# eom_test_pcb_v2.net
KiCad netlist of a schematic drawn in EAGLE
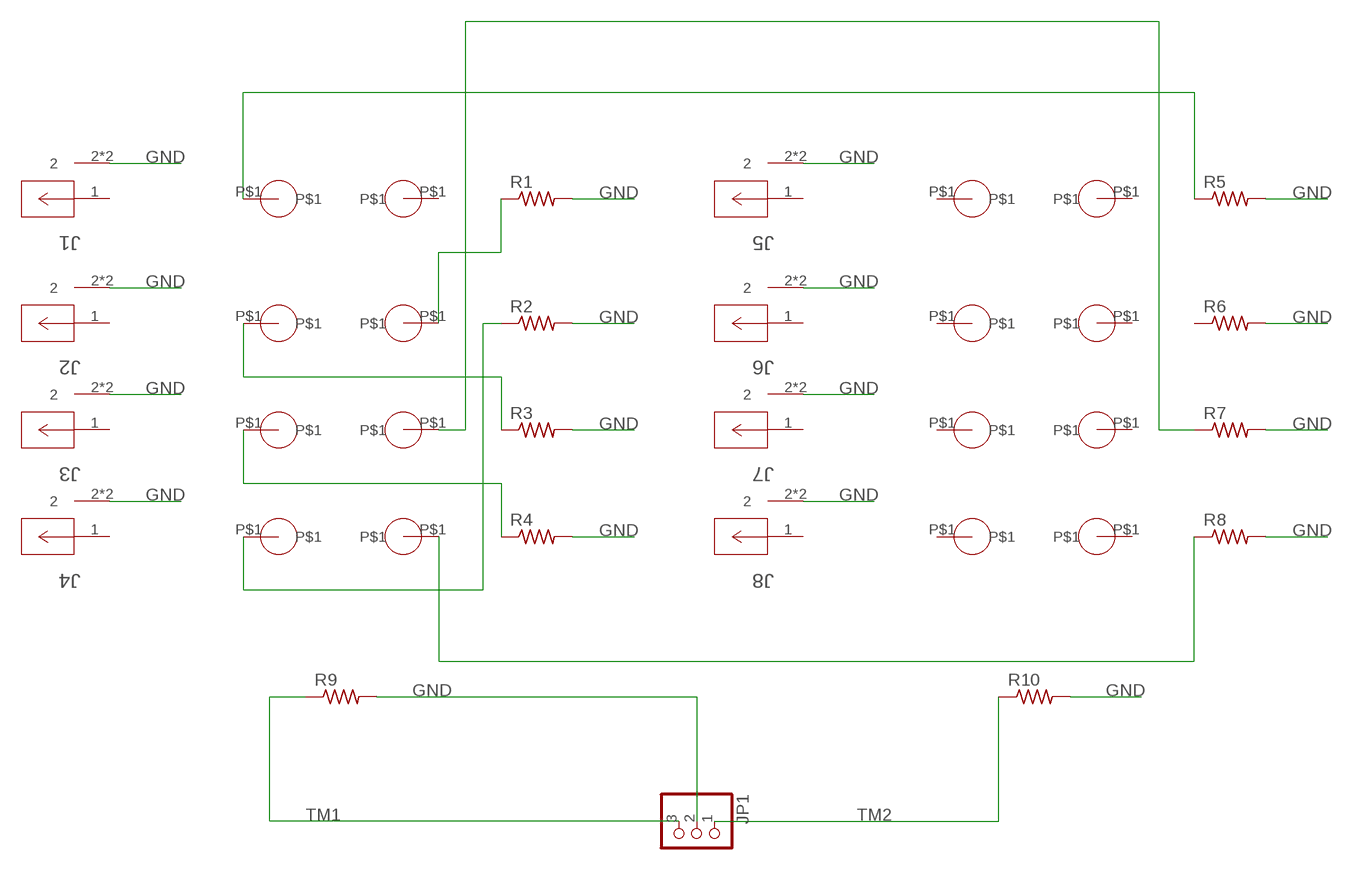
[diagram p0: schematic, sheet 1]

(export (version "E")
  (design (tool "Eeschema 10.0.6"))
  (components
    (comp (ref "J1")
      (value "142-0711-821")
      (footprint "eagle-import:CONN_142-0711-821_CIN")
      (fields (field (name "COPYRIGHT") "Copyright (C) 2021 Ultra Librarian. All rights reserved."))
      (libsource (lib "eagle-import") (part "142-0711-821"))
    )
    (comp (ref "J2")
      (value "142-0711-821")
      (footprint "eagle-import:CONN_142-0711-821_CIN")
      (fields (field (name "COPYRIGHT") "Copyright (C) 2021 Ultra Librarian. All rights reserved."))
      (libsource (lib "eagle-import") (part "142-0711-821"))
    )
    (comp (ref "J3")
      (value "142-0711-821")
      (footprint "eagle-import:CONN_142-0711-821_CIN")
      (fields (field (name "COPYRIGHT") "Copyright (C) 2021 Ultra Librarian. All rights reserved."))
      (libsource (lib "eagle-import") (part "142-0711-821"))
    )
    (comp (ref "J4")
      (value "142-0711-821")
      (footprint "eagle-import:CONN_142-0711-821_CIN")
      (fields (field (name "COPYRIGHT") "Copyright (C) 2021 Ultra Librarian. All rights reserved."))
      (libsource (lib "eagle-import") (part "142-0711-821"))
    )
    (comp (ref "J5")
      (value "142-0711-821")
      (footprint "eagle-import:CONN_142-0711-821_CIN")
      (fields (field (name "COPYRIGHT") "Copyright (C) 2021 Ultra Librarian. All rights reserved."))
      (libsource (lib "eagle-import") (part "142-0711-821"))
    )
    (comp (ref "J6")
      (value "142-0711-821")
      (footprint "eagle-import:CONN_142-0711-821_CIN")
      (fields (field (name "COPYRIGHT") "Copyright (C) 2021 Ultra Librarian. All rights reserved."))
      (libsource (lib "eagle-import") (part "142-0711-821"))
    )
    (comp (ref "J7")
      (value "142-0711-821")
      (footprint "eagle-import:CONN_142-0711-821_CIN")
      (fields (field (name "COPYRIGHT") "Copyright (C) 2021 Ultra Librarian. All rights reserved."))
      (libsource (lib "eagle-import") (part "142-0711-821"))
    )
    (comp (ref "J8")
      (value "142-0711-821")
      (footprint "eagle-import:CONN_142-0711-821_CIN")
      (fields (field (name "COPYRIGHT") "Copyright (C) 2021 Ultra Librarian. All rights reserved."))
      (libsource (lib "eagle-import") (part "142-0711-821"))
    )
    (comp (ref "JP1")
      (value "PINHD-1X3")
      (footprint "eagle-import:1X03")
      (libsource (lib "eagle-import") (part "PINHD-1X3"))
    )
    (comp (ref "R1")
      (value "R-US_M1206")
      (footprint "eagle-import:M1206")
      (libsource (lib "eagle-import") (part "R-US_M1206"))
    )
    (comp (ref "R2")
      (value "R-US_M1206")
      (footprint "eagle-import:M1206")
      (libsource (lib "eagle-import") (part "R-US_M1206"))
    )
    (comp (ref "R3")
      (value "R-US_M1206")
      (footprint "eagle-import:M1206")
      (libsource (lib "eagle-import") (part "R-US_M1206"))
    )
    (comp (ref "R4")
      (value "R-US_M1206")
      (footprint "eagle-import:M1206")
      (libsource (lib "eagle-import") (part "R-US_M1206"))
    )
    (comp (ref "R5")
      (value "R-US_M1206")
      (footprint "eagle-import:M1206")
      (libsource (lib "eagle-import") (part "R-US_M1206"))
    )
    (comp (ref "R6")
      (value "R-US_M1206")
      (footprint "eagle-import:M1206")
      (libsource (lib "eagle-import") (part "R-US_M1206"))
    )
    (comp (ref "R7")
      (value "R-US_M1206")
      (footprint "eagle-import:M1206")
      (libsource (lib "eagle-import") (part "R-US_M1206"))
    )
    (comp (ref "R8")
      (value "R-US_M1206")
      (footprint "eagle-import:M1206")
      (libsource (lib "eagle-import") (part "R-US_M1206"))
    )
    (comp (ref "R9")
      (value "R-US_R0402")
      (footprint "eagle-import:R0402")
      (libsource (lib "eagle-import") (part "adafruit_420_R-US_R0402"))
    )
    (comp (ref "R10")
      (value "R-US_R0402")
      (footprint "eagle-import:R0402")
      (libsource (lib "eagle-import") (part "adafruit_420_R-US_R0402"))
    )
    (comp (ref "U$1")
      (value "SIGNAL_BONDING_DEVICE")
      (footprint "eagle-import:SIGNAL_BONDING_PAD")
      (libsource (lib "eagle-import") (part "SIGNAL_BONDING_DEVICE"))
    )
    (comp (ref "U$2")
      (value "SIGNAL_BONDING_DEVICE")
      (footprint "eagle-import:SIGNAL_BONDING_PAD")
      (libsource (lib "eagle-import") (part "SIGNAL_BONDING_DEVICE"))
    )
    (comp (ref "U$3")
      (value "SIGNAL_BONDING_DEVICE")
      (footprint "eagle-import:SIGNAL_BONDING_PAD")
      (libsource (lib "eagle-import") (part "SIGNAL_BONDING_DEVICE"))
    )
    (comp (ref "U$4")
      (value "SIGNAL_BONDING_DEVICE")
      (footprint "eagle-import:SIGNAL_BONDING_PAD")
      (libsource (lib "eagle-import") (part "SIGNAL_BONDING_DEVICE"))
    )
    (comp (ref "U$5")
      (value "SIGNAL_BONDING_DEVICE")
      (footprint "eagle-import:SIGNAL_BONDING_PAD")
      (libsource (lib "eagle-import") (part "SIGNAL_BONDING_DEVICE"))
    )
    (comp (ref "U$6")
      (value "SIGNAL_BONDING_DEVICE")
      (footprint "eagle-import:SIGNAL_BONDING_PAD")
      (libsource (lib "eagle-import") (part "SIGNAL_BONDING_DEVICE"))
    )
    (comp (ref "U$7")
      (value "SIGNAL_BONDING_DEVICE")
      (footprint "eagle-import:SIGNAL_BONDING_PAD")
      (libsource (lib "eagle-import") (part "SIGNAL_BONDING_DEVICE"))
    )
    (comp (ref "U$8")
      (value "SIGNAL_BONDING_DEVICE")
      (footprint "eagle-import:SIGNAL_BONDING_PAD")
      (libsource (lib "eagle-import") (part "SIGNAL_BONDING_DEVICE"))
    )
    (comp (ref "U$9")
      (value "SIGNAL_BONDING_DEVICE")
      (footprint "eagle-import:SIGNAL_BONDING_PAD")
      (libsource (lib "eagle-import") (part "SIGNAL_BONDING_DEVICE"))
    )
    (comp (ref "U$10")
      (value "SIGNAL_BONDING_DEVICE")
      (footprint "eagle-import:SIGNAL_BONDING_PAD")
      (libsource (lib "eagle-import") (part "SIGNAL_BONDING_DEVICE"))
    )
    (comp (ref "U$11")
      (value "SIGNAL_BONDING_DEVICE")
      (footprint "eagle-import:SIGNAL_BONDING_PAD")
      (libsource (lib "eagle-import") (part "SIGNAL_BONDING_DEVICE"))
    )
    (comp (ref "U$12")
      (value "SIGNAL_BONDING_DEVICE")
      (footprint "eagle-import:SIGNAL_BONDING_PAD")
      (libsource (lib "eagle-import") (part "SIGNAL_BONDING_DEVICE"))
    )
    (comp (ref "U$13")
      (value "SIGNAL_BONDING_DEVICE")
      (footprint "eagle-import:SIGNAL_BONDING_PAD")
      (libsource (lib "eagle-import") (part "SIGNAL_BONDING_DEVICE"))
    )
    (comp (ref "U$14")
      (value "SIGNAL_BONDING_DEVICE")
      (footprint "eagle-import:SIGNAL_BONDING_PAD")
      (libsource (lib "eagle-import") (part "SIGNAL_BONDING_DEVICE"))
    )
    (comp (ref "U$15")
      (value "SIGNAL_BONDING_DEVICE")
      (footprint "eagle-import:SIGNAL_BONDING_PAD")
      (libsource (lib "eagle-import") (part "SIGNAL_BONDING_DEVICE"))
    )
    (comp (ref "U$16")
      (value "SIGNAL_BONDING_DEVICE")
      (footprint "eagle-import:SIGNAL_BONDING_PAD")
      (libsource (lib "eagle-import") (part "SIGNAL_BONDING_DEVICE"))
    )
  )
  (nets
    (net (code "1") (name "/GND") (class "Default")
      (node (ref "J1") (pin "2") (pinfunction "2_2") (pintype "bidirectional"))
      (node (ref "J1") (pin "3") (pinfunction "2_3") (pintype "bidirectional"))
      (node (ref "J2") (pin "2") (pinfunction "2_2") (pintype "bidirectional"))
      (node (ref "J2") (pin "3") (pinfunction "2_3") (pintype "bidirectional"))
      (node (ref "J3") (pin "2") (pinfunction "2_2") (pintype "bidirectional"))
      (node (ref "J3") (pin "3") (pinfunction "2_3") (pintype "bidirectional"))
      (node (ref "J4") (pin "2") (pinfunction "2_2") (pintype "bidirectional"))
      (node (ref "J4") (pin "3") (pinfunction "2_3") (pintype "bidirectional"))
      (node (ref "J5") (pin "2") (pinfunction "2_2") (pintype "bidirectional"))
      (node (ref "J5") (pin "3") (pinfunction "2_3") (pintype "bidirectional"))
      (node (ref "J6") (pin "2") (pinfunction "2_2") (pintype "bidirectional"))
      (node (ref "J6") (pin "3") (pinfunction "2_3") (pintype "bidirectional"))
      (node (ref "J7") (pin "2") (pinfunction "2_2") (pintype "bidirectional"))
      (node (ref "J7") (pin "3") (pinfunction "2_3") (pintype "bidirectional"))
      (node (ref "J8") (pin "2") (pinfunction "2_2") (pintype "bidirectional"))
      (node (ref "J8") (pin "3") (pinfunction "2_3") (pintype "bidirectional"))
      (node (ref "JP1") (pin "2") (pinfunction "2_2") (pintype "passive"))
      (node (ref "R1") (pin "2") (pinfunction "2_2") (pintype "passive"))
      (node (ref "R10") (pin "2") (pinfunction "2_2") (pintype "passive"))
      (node (ref "R2") (pin "2") (pinfunction "2_2") (pintype "passive"))
      (node (ref "R3") (pin "2") (pinfunction "2_2") (pintype "passive"))
      (node (ref "R4") (pin "2") (pinfunction "2_2") (pintype "passive"))
      (node (ref "R5") (pin "2") (pinfunction "2_2") (pintype "passive"))
      (node (ref "R6") (pin "2") (pinfunction "2_2") (pintype "passive"))
      (node (ref "R7") (pin "2") (pinfunction "2_2") (pintype "passive"))
      (node (ref "R8") (pin "2") (pinfunction "2_2") (pintype "passive"))
      (node (ref "R9") (pin "2") (pinfunction "2_2") (pintype "passive"))
    )
    (net (code "2") (name "/TM1") (class "Default")
      (node (ref "JP1") (pin "3") (pinfunction "3_3") (pintype "passive"))
      (node (ref "R9") (pin "1") (pinfunction "1_1") (pintype "passive"))
    )
    (net (code "3") (name "/TM2") (class "Default")
      (node (ref "JP1") (pin "1") (pinfunction "1_1") (pintype "passive"))
      (node (ref "R10") (pin "1") (pinfunction "1_1") (pintype "passive"))
    )
    (net (code "4") (name "Net-(R1-Pad1)") (class "Default")
      (node (ref "R1") (pin "1") (pinfunction "1_1") (pintype "passive"))
      (node (ref "U$4") (pin "P$1") (pinfunction "P$1_P$1") (pintype "bidirectional"))
    )
    (net (code "5") (name "Net-(R2-Pad1)") (class "Default")
      (node (ref "R2") (pin "1") (pinfunction "1_1") (pintype "passive"))
      (node (ref "U$7") (pin "P$1") (pinfunction "P$1_P$1") (pintype "bidirectional"))
    )
    (net (code "6") (name "Net-(R3-Pad1)") (class "Default")
      (node (ref "R3") (pin "1") (pinfunction "1_1") (pintype "passive"))
      (node (ref "U$3") (pin "P$1") (pinfunction "P$1_P$1") (pintype "bidirectional"))
    )
    (net (code "7") (name "Net-(R4-Pad1)") (class "Default")
      (node (ref "R4") (pin "1") (pinfunction "1_1") (pintype "passive"))
      (node (ref "U$5") (pin "P$1") (pinfunction "P$1_P$1") (pintype "bidirectional"))
    )
    (net (code "8") (name "Net-(R5-Pad1)") (class "Default")
      (node (ref "R5") (pin "1") (pinfunction "1_1") (pintype "passive"))
      (node (ref "U$1") (pin "P$1") (pinfunction "P$1_P$1") (pintype "bidirectional"))
    )
    (net (code "9") (name "Net-(R7-Pad1)") (class "Default")
      (node (ref "R7") (pin "1") (pinfunction "1_1") (pintype "passive"))
      (node (ref "U$6") (pin "P$1") (pinfunction "P$1_P$1") (pintype "bidirectional"))
    )
    (net (code "10") (name "Net-(R8-Pad1)") (class "Default")
      (node (ref "R8") (pin "1") (pinfunction "1_1") (pintype "passive"))
      (node (ref "U$8") (pin "P$1") (pinfunction "P$1_P$1") (pintype "bidirectional"))
    )
    (net (code "11") (name "unconnected-(J1-Pad1)") (class "Default")
      (node (ref "J1") (pin "1") (pinfunction "1_1") (pintype "passive"))
    )
    (net (code "12") (name "unconnected-(J2-Pad1)") (class "Default")
      (node (ref "J2") (pin "1") (pinfunction "1_1") (pintype "passive"))
    )
    (net (code "13") (name "unconnected-(J3-Pad1)") (class "Default")
      (node (ref "J3") (pin "1") (pinfunction "1_1") (pintype "passive"))
    )
    (net (code "14") (name "unconnected-(J4-Pad1)") (class "Default")
      (node (ref "J4") (pin "1") (pinfunction "1_1") (pintype "passive"))
    )
    (net (code "15") (name "unconnected-(J5-Pad1)") (class "Default")
      (node (ref "J5") (pin "1") (pinfunction "1_1") (pintype "passive"))
    )
    (net (code "16") (name "unconnected-(J6-Pad1)") (class "Default")
      (node (ref "J6") (pin "1") (pinfunction "1_1") (pintype "passive"))
    )
    (net (code "17") (name "unconnected-(J7-Pad1)") (class "Default")
      (node (ref "J7") (pin "1") (pinfunction "1_1") (pintype "passive"))
    )
    (net (code "18") (name "unconnected-(J8-Pad1)") (class "Default")
      (node (ref "J8") (pin "1") (pinfunction "1_1") (pintype "passive"))
    )
    (net (code "19") (name "unconnected-(R6-Pad1)") (class "Default")
      (node (ref "R6") (pin "1") (pinfunction "1_1") (pintype "passive"))
    )
    (net (code "20") (name "unconnected-(U$2-PadP$1)") (class "Default")
      (node (ref "U$2") (pin "P$1") (pinfunction "P$1_P$1") (pintype "bidirectional"))
    )
    (net (code "21") (name "unconnected-(U$9-PadP$1)") (class "Default")
      (node (ref "U$9") (pin "P$1") (pinfunction "P$1_P$1") (pintype "bidirectional"))
    )
    (net (code "22") (name "unconnected-(U$10-PadP$1)") (class "Default")
      (node (ref "U$10") (pin "P$1") (pinfunction "P$1_P$1") (pintype "bidirectional"))
    )
    (net (code "23") (name "unconnected-(U$11-PadP$1)") (class "Default")
      (node (ref "U$11") (pin "P$1") (pinfunction "P$1_P$1") (pintype "bidirectional"))
    )
    (net (code "24") (name "unconnected-(U$12-PadP$1)") (class "Default")
      (node (ref "U$12") (pin "P$1") (pinfunction "P$1_P$1") (pintype "bidirectional"))
    )
    (net (code "25") (name "unconnected-(U$13-PadP$1)") (class "Default")
      (node (ref "U$13") (pin "P$1") (pinfunction "P$1_P$1") (pintype "bidirectional"))
    )
    (net (code "26") (name "unconnected-(U$14-PadP$1)") (class "Default")
      (node (ref "U$14") (pin "P$1") (pinfunction "P$1_P$1") (pintype "bidirectional"))
    )
    (net (code "27") (name "unconnected-(U$15-PadP$1)") (class "Default")
      (node (ref "U$15") (pin "P$1") (pinfunction "P$1_P$1") (pintype "bidirectional"))
    )
    (net (code "28") (name "unconnected-(U$16-PadP$1)") (class "Default")
      (node (ref "U$16") (pin "P$1") (pinfunction "P$1_P$1") (pintype "bidirectional"))
    )
  )
)
